# SCH_openELECTRO_-_ArduinoUNO_-_OVEN_2022.net
KiCad netlist of a schematic drawn in EasyEDA
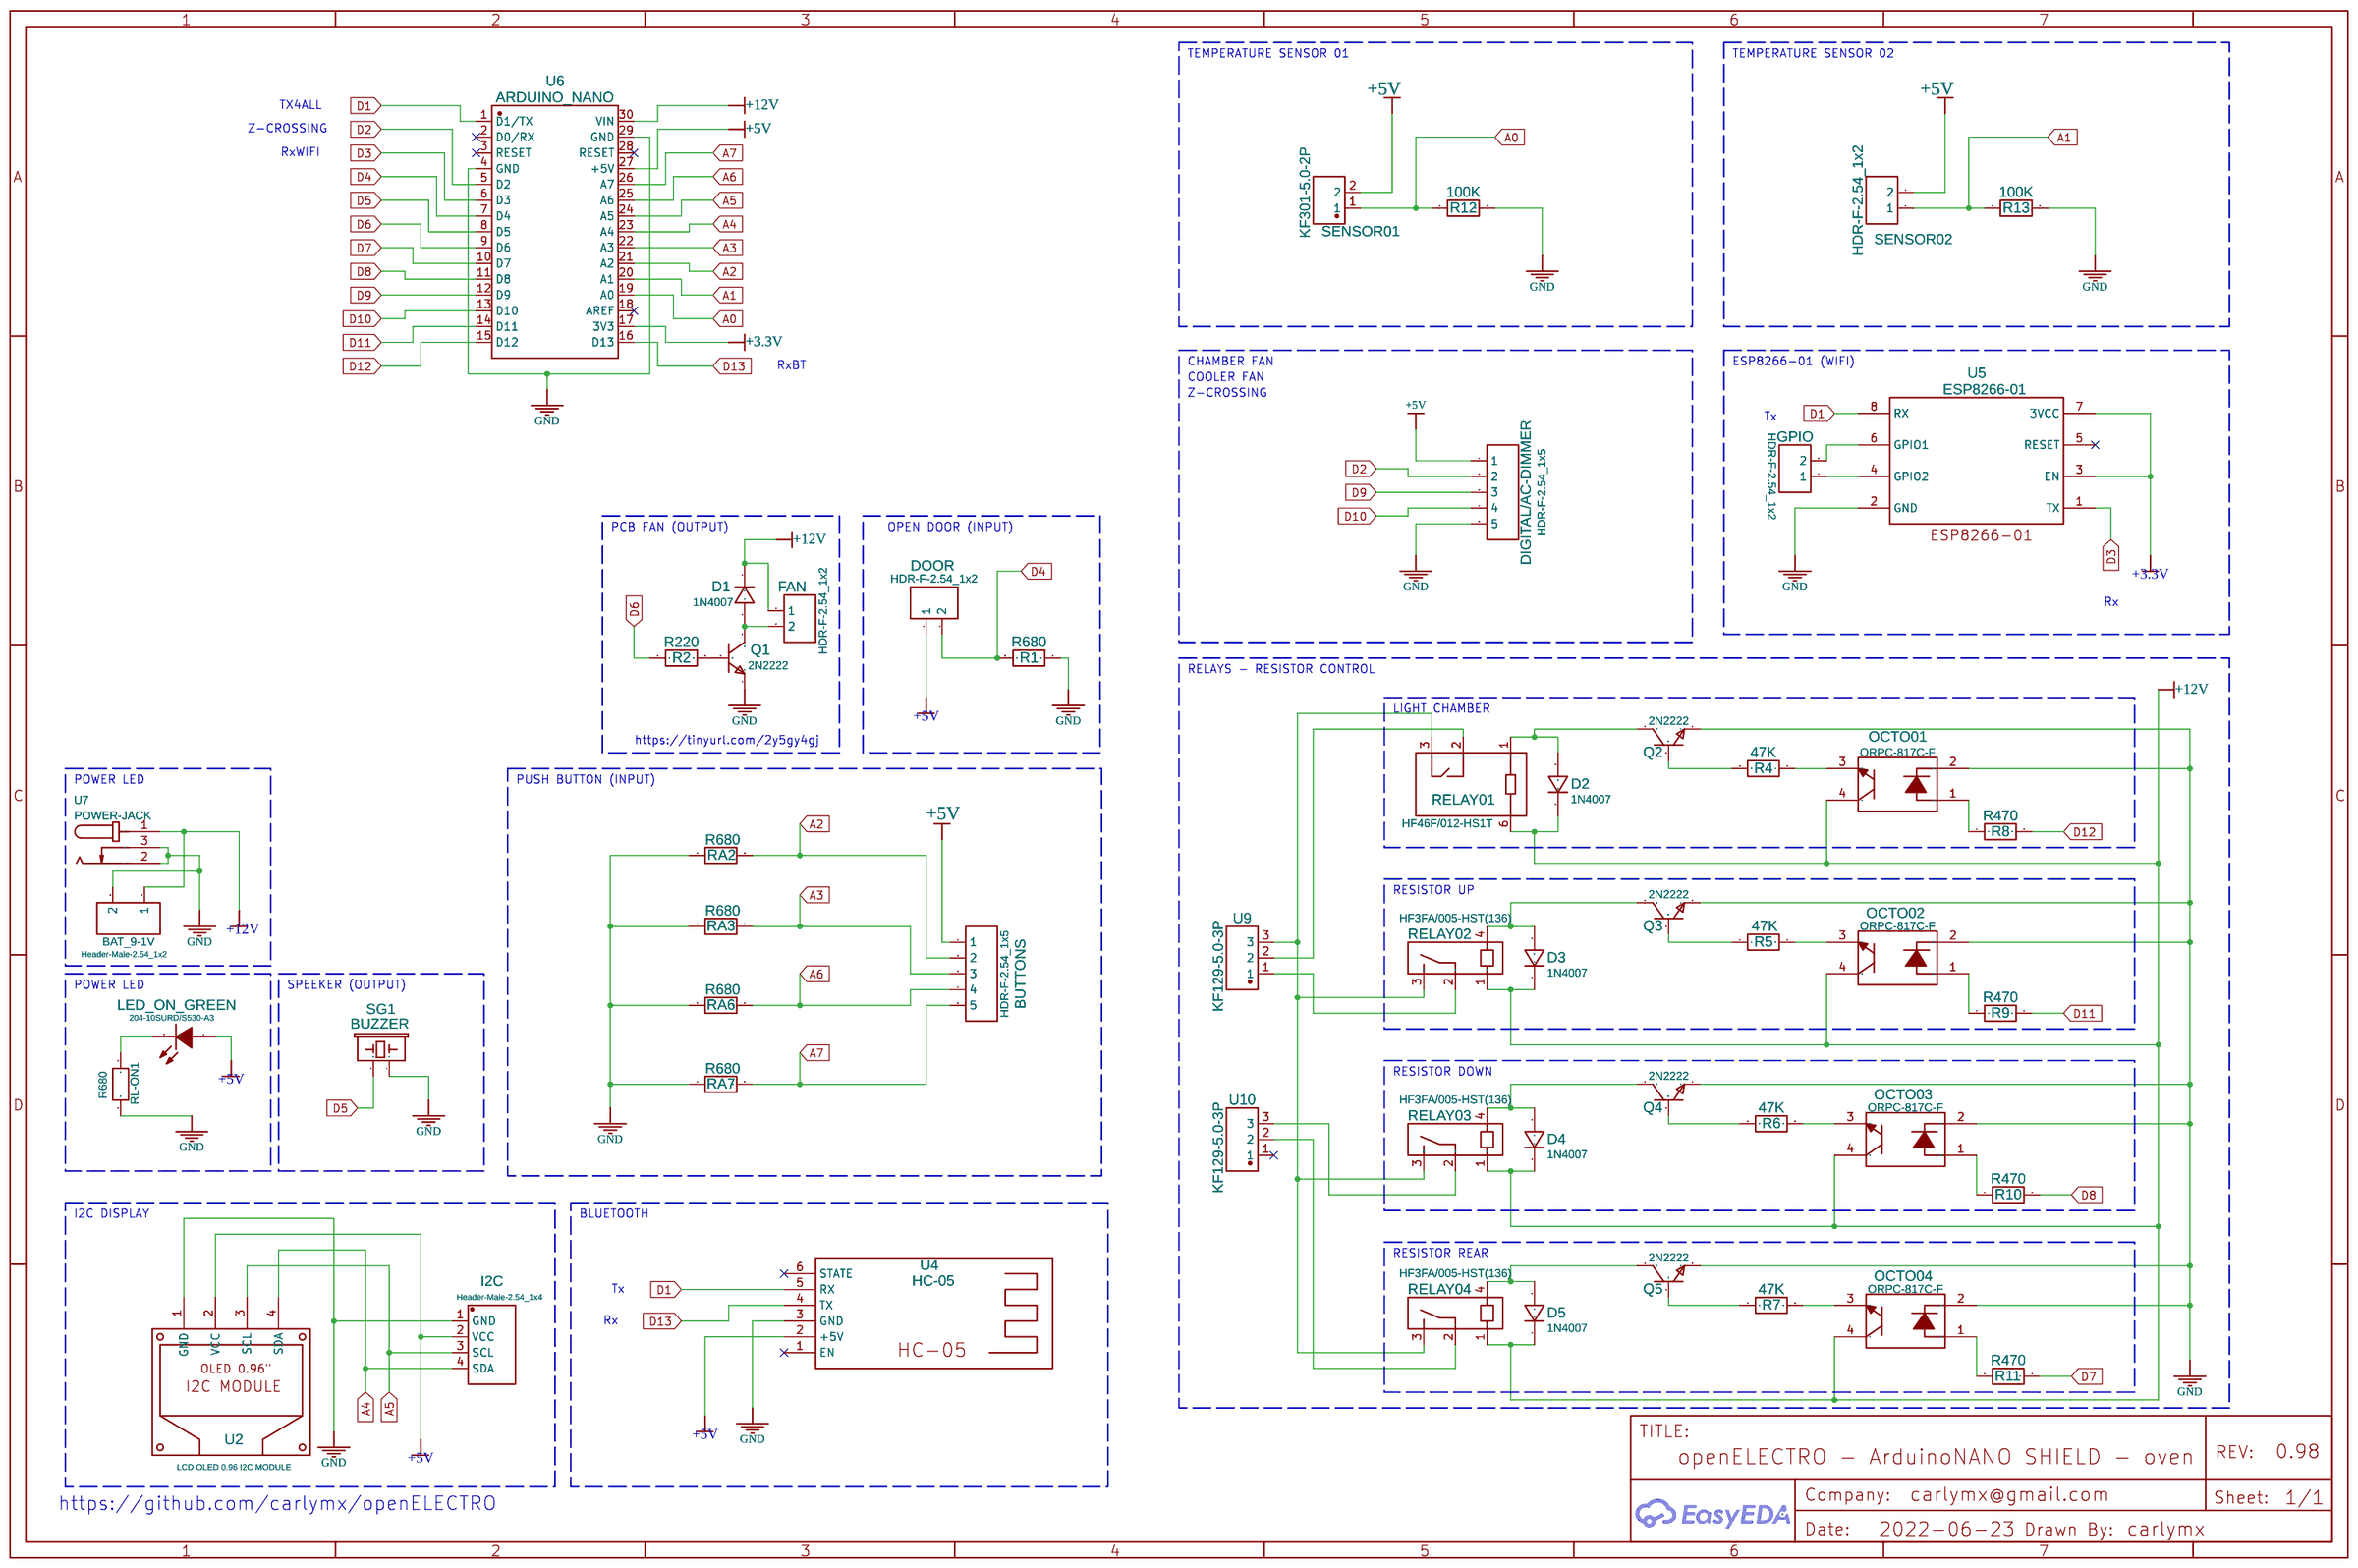
[diagram p0: schematic sheet]

(export (version "E")
  (design (tool "Eeschema 10.0.6"))
  (components
    (comp (ref "BAT_9-1V")
      (value "Header-Male-2.54_1x2")
      (fields (field (name "BOM_Manufacturer Part") "826629-2") (field (name "BOM_Supplier Part") "C86471"))
      (libsource (lib "") (part "Unknown_65_-400"))
    )
    (comp (ref "BUTTONS")
      (value "HDR-F-2.54_1x5")
      (fields (field (name "BOM_Supplier Part") "C50950"))
      (libsource (lib "") (part "HDR-F-2.54_1x5"))
    )
    (comp (ref "D1")
      (value "1N4007")
      (fields (field (name "BOM_Supplier Part") "C106903"))
      (libsource (lib "") (part "1N4007"))
    )
    (comp (ref "D2")
      (value "1N4007")
      (fields (field (name "BOM_Supplier Part") "C106903"))
      (libsource (lib "") (part "1N4007_1"))
    )
    (comp (ref "D3")
      (value "1N4007")
      (fields (field (name "BOM_Supplier Part") "C106903"))
      (libsource (lib "") (part "1N4007_1"))
    )
    (comp (ref "D4")
      (value "1N4007")
      (fields (field (name "BOM_Supplier Part") "C106903"))
      (libsource (lib "") (part "1N4007_1"))
    )
    (comp (ref "D5")
      (value "1N4007")
      (fields (field (name "BOM_Supplier Part") "C106903"))
      (libsource (lib "") (part "1N4007_1"))
    )
    (comp (ref "DIGITAL/AC-DIMMER")
      (value "HDR-F-2.54_1x5")
      (fields (field (name "BOM_Supplier Part") "C50950"))
      (libsource (lib "") (part "HDR-F-2.54_1x5_1"))
    )
    (comp (ref "DOOR")
      (value "HDR-F-2.54_1x2")
      (fields (field (name "BOM_Supplier Part") "C49661"))
      (libsource (lib "") (part "HDR-F-2.54_1x2_3"))
    )
    (comp (ref "FAN")
      (value "HDR-F-2.54_1x2")
      (fields (field (name "BOM_Supplier Part") "C49661"))
      (libsource (lib "") (part "HDR-F-2.54_1x2_1"))
    )
    (comp (ref "GPIO")
      (value "HDR-F-2.54_1x2")
      (fields (field (name "BOM_Supplier Part") "C49661"))
      (libsource (lib "") (part "HDR-F-2.54_1x2"))
    )
    (comp (ref "I2C")
      (value "Header-Male-2.54_1x4")
      (fields
        (field (name "BOM_Manufacturer Part") "210S-1*4P L=11.6MMGold-plated black")
        (field (name "BOM_Supplier Part") "C124378")
      )
      (libsource (lib "") (part "Unknown_290_-125"))
    )
    (comp (ref "LED_ON_GREEN")
      (value "204-10SURD/S530-A3")
      (fields (field (name "BOM_Supplier Part") "C99772"))
      (libsource (lib "") (part "Unknown_100_-315"))
    )
    (comp (ref "OCTO01")
      (value "ORPC-817C-F")
      (fields (field (name "BOM_Supplier Part") "C2842770"))
      (libsource (lib "") (part "ORPC-817C-F"))
    )
    (comp (ref "OCTO02")
      (value "ORPC-817C-F")
      (fields (field (name "BOM_Supplier Part") "C2842770"))
      (libsource (lib "") (part "ORPC-817C-F"))
    )
    (comp (ref "OCTO03")
      (value "ORPC-817C-F")
      (fields (field (name "BOM_Supplier Part") "C2842770"))
      (libsource (lib "") (part "ORPC-817C-F"))
    )
    (comp (ref "OCTO04")
      (value "ORPC-817C-F")
      (fields (field (name "BOM_Supplier Part") "C2842770"))
      (libsource (lib "") (part "ORPC-817C-F"))
    )
    (comp (ref "Q1")
      (value "2N2222")
      (fields (field (name "BOM_Supplier Part") "C118536"))
      (libsource (lib "") (part "2N2222_1"))
    )
    (comp (ref "Q2")
      (value "2N2222")
      (fields (field (name "BOM_Supplier Part") "C118536"))
      (libsource (lib "") (part "2N2222"))
    )
    (comp (ref "Q3")
      (value "2N2222")
      (fields (field (name "BOM_Supplier Part") "C118536"))
      (libsource (lib "") (part "2N2222"))
    )
    (comp (ref "Q4")
      (value "2N2222")
      (fields (field (name "BOM_Supplier Part") "C118536"))
      (libsource (lib "") (part "2N2222"))
    )
    (comp (ref "Q5")
      (value "2N2222")
      (fields (field (name "BOM_Supplier Part") "C118536"))
      (libsource (lib "") (part "2N2222"))
    )
    (comp (ref "R1") (value "R680") (libsource (lib "") (part "R_0603_EU_1")))
    (comp (ref "R2") (value "R220") (libsource (lib "") (part "R_0603_EU")))
    (comp (ref "R4") (value "47K") (libsource (lib "") (part "R_0603_EU_1")))
    (comp (ref "R5") (value "47K") (libsource (lib "") (part "R_0603_EU")))
    (comp (ref "R6") (value "47K") (libsource (lib "") (part "R_0603_EU")))
    (comp (ref "R7") (value "47K") (libsource (lib "") (part "R_0603_EU")))
    (comp (ref "R8") (value "R470") (libsource (lib "") (part "R_0603_EU")))
    (comp (ref "R9") (value "R470") (libsource (lib "") (part "R_0603_EU")))
    (comp (ref "R10") (value "R470") (libsource (lib "") (part "R_0603_EU")))
    (comp (ref "R11") (value "R470") (libsource (lib "") (part "R_0603_EU")))
    (comp (ref "R12") (value "100K") (libsource (lib "") (part "R_0603_EU")))
    (comp (ref "R13") (value "100K") (libsource (lib "") (part "R_0603_EU")))
    (comp (ref "RA2") (value "R680") (libsource (lib "") (part "Res_AXIAL-0.3(1/8W)_EU")))
    (comp (ref "RA3") (value "R680") (libsource (lib "") (part "Res_AXIAL-0.3(1/8W)_EU")))
    (comp (ref "RA6") (value "R680") (libsource (lib "") (part "Res_AXIAL-0.3(1/8W)_EU")))
    (comp (ref "RA7") (value "R680") (libsource (lib "") (part "Res_AXIAL-0.3(1/8W)_EU")))
    (comp (ref "RELAY01")
      (value "HF46F/012-HS1T")
      (fields (field (name "BOM_Supplier Part") "C2976852"))
      (libsource (lib "") (part "HF46F/012-HS1T"))
    )
    (comp (ref "RELAY02")
      (value "HF3FA/005-HST(136)")
      (fields (field (name "BOM_Supplier Part") "C712707"))
      (libsource (lib "") (part "HF3FA/005-HST(136)"))
    )
    (comp (ref "RELAY03")
      (value "HF3FA/005-HST(136)")
      (fields (field (name "BOM_Supplier Part") "C712707"))
      (libsource (lib "") (part "HF3FA/005-HST(136)"))
    )
    (comp (ref "RELAY04")
      (value "HF3FA/005-HST(136)")
      (fields (field (name "BOM_Supplier Part") "C712707"))
      (libsource (lib "") (part "HF3FA/005-HST(136)"))
    )
    (comp (ref "RL-ON1") (value "R680") (libsource (lib "") (part "Res_AXIAL-0.3(1/8W)_EU_1")))
    (comp (ref "SENSOR01")
      (value "KF301-5.0-2P")
      (fields (field (name "BOM_Supplier Part") "C474881"))
      (libsource (lib "") (part "KF301-5.0-2P"))
    )
    (comp (ref "SENSOR02")
      (value "HDR-F-2.54_1x2")
      (fields (field (name "BOM_Supplier Part") "C49661"))
      (libsource (lib "") (part "HDR-F-2.54_1x2_2"))
    )
    (comp (ref "SG1") (value "BUZZER") (libsource (lib "") (part "Unknown_225_-305")))
    (comp (ref "U2")
      (value "LCD OLED 0.96 I2C MODULE")
      (fields (field (name "BOM_Manufacturer Part") "Control Chip SSD1306"))
      (libsource (lib "") (part "Unknown_80_-135"))
    )
    (comp (ref "U4") (value "HC-05") (libsource (lib "") (part "Unknown_500_-180")))
    (comp (ref "U5") (value "ESP8266-01") (libsource (lib "") (part "ESP8266-01")))
    (comp (ref "U6")
      (value "ARDUINO_NANO")
      (fields (field (name "BOM_Supplier Part") "C9900017879"))
      (libsource (lib "") (part "ARDUINO_NANO"))
    )
    (comp (ref "U7")
      (value "POWER-JACK")
      (fields (field (name "BOM_Supplier Part") "C9900001795"))
      (libsource (lib "") (part "POWER-JACK"))
    )
    (comp (ref "U9")
      (value "KF129-5.0-3P")
      (fields (field (name "BOM_Supplier Part") "C475091"))
      (libsource (lib "") (part "KF129-5.0-3P"))
    )
    (comp (ref "U10")
      (value "KF129-5.0-3P")
      (fields (field (name "BOM_Supplier Part") "C475091"))
      (libsource (lib "") (part "KF129-5.0-3P"))
    )
  )
  (nets
    (net (code "1") (name "+3.3V") (class "Default")
      (node (ref "U5") (pin "3") (pinfunction "EN_3") (pintype "unspecified"))
      (node (ref "U5") (pin "7") (pinfunction "3VCC_7") (pintype "unspecified"))
      (node (ref "U6") (pin "17") (pinfunction "3V3_17") (pintype "unspecified"))
    )
    (net (code "2") (name "+5V") (class "Default")
      (node (ref "BUTTONS") (pin "1") (pinfunction "1_1") (pintype "unspecified"))
      (node (ref "DIGITAL/AC-DIMMER") (pin "1") (pinfunction "1_1") (pintype "unspecified"))
      (node (ref "DOOR") (pin "1") (pinfunction "1_1") (pintype "input"))
      (node (ref "I2C") (pin "2") (pinfunction "VCC_2") (pintype "unspecified"))
      (node (ref "LED_ON_GREEN") (pin "1") (pinfunction "A_1") (pintype "unspecified"))
      (node (ref "SENSOR01") (pin "2") (pinfunction "2_2") (pintype "unspecified"))
      (node (ref "SENSOR02") (pin "2") (pinfunction "2_2") (pintype "input"))
      (node (ref "U2") (pin "2") (pinfunction "VCC_2") (pintype "unspecified"))
      (node (ref "U4") (pin "2") (pinfunction "+5V_2") (pintype "unspecified"))
      (node (ref "U6") (pin "27") (pinfunction "+5V_27") (pintype "unspecified"))
    )
    (net (code "3") (name "+12V") (class "Default")
      (node (ref "BAT_9-1V") (pin "1") (pinfunction "1_1") (pintype "unspecified"))
      (node (ref "D1") (pin "1") (pinfunction "1_1") (pintype "unspecified"))
      (node (ref "D2") (pin "1") (pinfunction "1_1") (pintype "unspecified"))
      (node (ref "D3") (pin "1") (pinfunction "1_1") (pintype "unspecified"))
      (node (ref "D4") (pin "1") (pinfunction "1_1") (pintype "unspecified"))
      (node (ref "D5") (pin "1") (pinfunction "1_1") (pintype "unspecified"))
      (node (ref "FAN") (pin "1") (pinfunction "1_1") (pintype "input"))
      (node (ref "OCTO01") (pin "4") (pinfunction "4_4") (pintype "unspecified"))
      (node (ref "OCTO02") (pin "4") (pinfunction "4_4") (pintype "unspecified"))
      (node (ref "OCTO03") (pin "4") (pinfunction "4_4") (pintype "unspecified"))
      (node (ref "OCTO04") (pin "4") (pinfunction "4_4") (pintype "unspecified"))
      (node (ref "RELAY01") (pin "6") (pinfunction "6_6") (pintype "unspecified"))
      (node (ref "RELAY02") (pin "1") (pinfunction "1_1") (pintype "unspecified"))
      (node (ref "RELAY03") (pin "1") (pinfunction "1_1") (pintype "unspecified"))
      (node (ref "RELAY04") (pin "1") (pinfunction "1_1") (pintype "unspecified"))
      (node (ref "U6") (pin "30") (pinfunction "VIN_30") (pintype "unspecified"))
      (node (ref "U7") (pin "1") (pinfunction "1_1") (pintype "unspecified"))
    )
    (net (code "4") (name "A0") (class "Default")
      (node (ref "R12") (pin "1") (pinfunction "1_1") (pintype "unspecified"))
      (node (ref "SENSOR01") (pin "1") (pinfunction "1_1") (pintype "unspecified"))
      (node (ref "U6") (pin "19") (pinfunction "A0_19") (pintype "unspecified"))
    )
    (net (code "5") (name "A1") (class "Default")
      (node (ref "R13") (pin "1") (pinfunction "1_1") (pintype "unspecified"))
      (node (ref "SENSOR02") (pin "1") (pinfunction "1_1") (pintype "input"))
      (node (ref "U6") (pin "20") (pinfunction "A1_20") (pintype "unspecified"))
    )
    (net (code "6") (name "A2") (class "Default")
      (node (ref "BUTTONS") (pin "2") (pinfunction "2_2") (pintype "unspecified"))
      (node (ref "RA2") (pin "2") (pinfunction "2_2") (pintype "unspecified"))
      (node (ref "U6") (pin "21") (pinfunction "A2_21") (pintype "unspecified"))
    )
    (net (code "7") (name "A3") (class "Default")
      (node (ref "BUTTONS") (pin "3") (pinfunction "3_3") (pintype "unspecified"))
      (node (ref "RA3") (pin "2") (pinfunction "2_2") (pintype "unspecified"))
      (node (ref "U6") (pin "22") (pinfunction "A3_22") (pintype "unspecified"))
    )
    (net (code "8") (name "A4") (class "Default")
      (node (ref "I2C") (pin "4") (pinfunction "SDA_4") (pintype "unspecified"))
      (node (ref "U2") (pin "4") (pinfunction "SDA_4") (pintype "unspecified"))
      (node (ref "U6") (pin "23") (pinfunction "A4_23") (pintype "unspecified"))
    )
    (net (code "9") (name "A5") (class "Default")
      (node (ref "I2C") (pin "3") (pinfunction "SCL_3") (pintype "unspecified"))
      (node (ref "U2") (pin "3") (pinfunction "SCL_3") (pintype "unspecified"))
      (node (ref "U6") (pin "24") (pinfunction "A5_24") (pintype "unspecified"))
    )
    (net (code "10") (name "A6") (class "Default")
      (node (ref "BUTTONS") (pin "4") (pinfunction "4_4") (pintype "unspecified"))
      (node (ref "RA6") (pin "2") (pinfunction "2_2") (pintype "unspecified"))
      (node (ref "U6") (pin "25") (pinfunction "A6_25") (pintype "unspecified"))
    )
    (net (code "11") (name "A7") (class "Default")
      (node (ref "BUTTONS") (pin "5") (pinfunction "5_5") (pintype "unspecified"))
      (node (ref "RA7") (pin "2") (pinfunction "2_2") (pintype "unspecified"))
      (node (ref "U6") (pin "26") (pinfunction "A7_26") (pintype "unspecified"))
    )
    (net (code "12") (name "D1") (class "Default")
      (node (ref "U4") (pin "5") (pinfunction "RX_5") (pintype "unspecified"))
      (node (ref "U5") (pin "8") (pinfunction "RX_8") (pintype "unspecified"))
      (node (ref "U6") (pin "1") (pinfunction "D1/TX_1") (pintype "unspecified"))
    )
    (net (code "13") (name "D2") (class "Default")
      (node (ref "DIGITAL/AC-DIMMER") (pin "2") (pinfunction "2_2") (pintype "unspecified"))
      (node (ref "U6") (pin "5") (pinfunction "D2_5") (pintype "unspecified"))
    )
    (net (code "14") (name "D3") (class "Default")
      (node (ref "U5") (pin "1") (pinfunction "TX_1") (pintype "unspecified"))
      (node (ref "U6") (pin "6") (pinfunction "D3_6") (pintype "unspecified"))
    )
    (net (code "15") (name "D4") (class "Default")
      (node (ref "DOOR") (pin "2") (pinfunction "2_2") (pintype "input"))
      (node (ref "R1") (pin "2") (pinfunction "2_2") (pintype "unspecified"))
      (node (ref "U6") (pin "7") (pinfunction "D4_7") (pintype "unspecified"))
    )
    (net (code "16") (name "D5") (class "Default")
      (node (ref "SG1") (pin "+") (pinfunction "1_+") (pintype "unspecified"))
      (node (ref "U6") (pin "8") (pinfunction "D5_8") (pintype "unspecified"))
    )
    (net (code "17") (name "D6") (class "Default")
      (node (ref "R2") (pin "1") (pinfunction "1_1") (pintype "unspecified"))
      (node (ref "U6") (pin "9") (pinfunction "D6_9") (pintype "unspecified"))
    )
    (net (code "18") (name "D7") (class "Default")
      (node (ref "R11") (pin "2") (pinfunction "2_2") (pintype "unspecified"))
      (node (ref "U6") (pin "10") (pinfunction "D7_10") (pintype "unspecified"))
    )
    (net (code "19") (name "D8") (class "Default")
      (node (ref "R10") (pin "2") (pinfunction "2_2") (pintype "unspecified"))
      (node (ref "U6") (pin "11") (pinfunction "D8_11") (pintype "unspecified"))
    )
    (net (code "20") (name "D9") (class "Default")
      (node (ref "DIGITAL/AC-DIMMER") (pin "3") (pinfunction "3_3") (pintype "unspecified"))
      (node (ref "U6") (pin "12") (pinfunction "D9_12") (pintype "unspecified"))
    )
    (net (code "21") (name "D10") (class "Default")
      (node (ref "DIGITAL/AC-DIMMER") (pin "4") (pinfunction "4_4") (pintype "unspecified"))
      (node (ref "U6") (pin "13") (pinfunction "D10_13") (pintype "unspecified"))
    )
    (net (code "22") (name "D11") (class "Default")
      (node (ref "R9") (pin "2") (pinfunction "2_2") (pintype "unspecified"))
      (node (ref "U6") (pin "14") (pinfunction "D11_14") (pintype "unspecified"))
    )
    (net (code "23") (name "D12") (class "Default")
      (node (ref "R8") (pin "2") (pinfunction "2_2") (pintype "unspecified"))
      (node (ref "U6") (pin "15") (pinfunction "D12_15") (pintype "unspecified"))
    )
    (net (code "24") (name "D13") (class "Default")
      (node (ref "U4") (pin "4") (pinfunction "TX_4") (pintype "unspecified"))
      (node (ref "U6") (pin "16") (pinfunction "D13_16") (pintype "unspecified"))
    )
    (net (code "25") (name "GND") (class "Default")
      (node (ref "BAT_9-1V") (pin "2") (pinfunction "2_2") (pintype "unspecified"))
      (node (ref "DIGITAL/AC-DIMMER") (pin "5") (pinfunction "5_5") (pintype "unspecified"))
      (node (ref "I2C") (pin "1") (pinfunction "GND_1") (pintype "unspecified"))
      (node (ref "OCTO01") (pin "2") (pinfunction "2_2") (pintype "unspecified"))
      (node (ref "OCTO02") (pin "2") (pinfunction "2_2") (pintype "unspecified"))
      (node (ref "OCTO03") (pin "2") (pinfunction "2_2") (pintype "unspecified"))
      (node (ref "OCTO04") (pin "2") (pinfunction "2_2") (pintype "unspecified"))
      (node (ref "Q1") (pin "1") (pinfunction "E_1") (pintype "unspecified"))
      (node (ref "Q2") (pin "1") (pinfunction "E_1") (pintype "unspecified"))
      (node (ref "Q3") (pin "1") (pinfunction "E_1") (pintype "unspecified"))
      (node (ref "Q4") (pin "1") (pinfunction "E_1") (pintype "unspecified"))
      (node (ref "Q5") (pin "1") (pinfunction "E_1") (pintype "unspecified"))
      (node (ref "R1") (pin "1") (pinfunction "1_1") (pintype "unspecified"))
      (node (ref "R12") (pin "2") (pinfunction "2_2") (pintype "unspecified"))
      (node (ref "R13") (pin "2") (pinfunction "2_2") (pintype "unspecified"))
      (node (ref "RA2") (pin "1") (pinfunction "1_1") (pintype "unspecified"))
      (node (ref "RA3") (pin "1") (pinfunction "1_1") (pintype "unspecified"))
      (node (ref "RA6") (pin "1") (pinfunction "1_1") (pintype "unspecified"))
      (node (ref "RA7") (pin "1") (pinfunction "1_1") (pintype "unspecified"))
      (node (ref "RL-ON1") (pin "1") (pinfunction "1_1") (pintype "unspecified"))
      (node (ref "SG1") (pin "-") (pinfunction "2_-") (pintype "unspecified"))
      (node (ref "U2") (pin "1") (pinfunction "GND_1") (pintype "unspecified"))
      (node (ref "U4") (pin "3") (pinfunction "GND_3") (pintype "unspecified"))
      (node (ref "U5") (pin "2") (pinfunction "GND_2") (pintype "unspecified"))
      (node (ref "U6") (pin "29") (pinfunction "GND_29") (pintype "unspecified"))
      (node (ref "U6") (pin "4") (pinfunction "GND_4") (pintype "unspecified"))
      (node (ref "U7") (pin "2") (pinfunction "2_2") (pintype "unspecified"))
      (node (ref "U7") (pin "3") (pinfunction "3_3") (pintype "unspecified"))
    )
    (net (code "26") (name "Net-(LED_ON_GREEN-K)") (class "Default")
      (node (ref "LED_ON_GREEN") (pin "2") (pinfunction "K_2") (pintype "unspecified"))
      (node (ref "RL-ON1") (pin "2") (pinfunction "2_2") (pintype "unspecified"))
    )
    (net (code "27") (name "Net-(OCTO01-Pad1)") (class "Default")
      (node (ref "OCTO01") (pin "1") (pinfunction "1_1") (pintype "unspecified"))
      (node (ref "R8") (pin "1") (pinfunction "1_1") (pintype "unspecified"))
    )
    (net (code "28") (name "Net-(OCTO01-Pad3)") (class "Default")
      (node (ref "OCTO01") (pin "3") (pinfunction "3_3") (pintype "unspecified"))
      (node (ref "R4") (pin "1") (pinfunction "1_1") (pintype "unspecified"))
    )
    (net (code "29") (name "Net-(OCTO02-Pad1)") (class "Default")
      (node (ref "OCTO02") (pin "1") (pinfunction "1_1") (pintype "unspecified"))
      (node (ref "R9") (pin "1") (pinfunction "1_1") (pintype "unspecified"))
    )
    (net (code "30") (name "Net-(OCTO02-Pad3)") (class "Default")
      (node (ref "OCTO02") (pin "3") (pinfunction "3_3") (pintype "unspecified"))
      (node (ref "R5") (pin "2") (pinfunction "2_2") (pintype "unspecified"))
    )
    (net (code "31") (name "Net-(OCTO03-Pad1)") (class "Default")
      (node (ref "OCTO03") (pin "1") (pinfunction "1_1") (pintype "unspecified"))
      (node (ref "R10") (pin "1") (pinfunction "1_1") (pintype "unspecified"))
    )
    (net (code "32") (name "Net-(OCTO03-Pad3)") (class "Default")
      (node (ref "OCTO03") (pin "3") (pinfunction "3_3") (pintype "unspecified"))
      (node (ref "R6") (pin "2") (pinfunction "2_2") (pintype "unspecified"))
    )
    (net (code "33") (name "Net-(OCTO04-Pad1)") (class "Default")
      (node (ref "OCTO04") (pin "1") (pinfunction "1_1") (pintype "unspecified"))
      (node (ref "R11") (pin "1") (pinfunction "1_1") (pintype "unspecified"))
    )
    (net (code "34") (name "Net-(OCTO04-Pad3)") (class "Default")
      (node (ref "OCTO04") (pin "3") (pinfunction "3_3") (pintype "unspecified"))
      (node (ref "R7") (pin "2") (pinfunction "2_2") (pintype "unspecified"))
    )
    (net (code "35") (name "Net-(Q1-B)") (class "Default")
      (node (ref "Q1") (pin "2") (pinfunction "B_2") (pintype "unspecified"))
      (node (ref "R2") (pin "2") (pinfunction "2_2") (pintype "unspecified"))
    )
    (net (code "36") (name "Net-(Q1-C)") (class "Default")
      (node (ref "D1") (pin "2") (pinfunction "2_2") (pintype "unspecified"))
      (node (ref "FAN") (pin "2") (pinfunction "2_2") (pintype "input"))
      (node (ref "Q1") (pin "3") (pinfunction "C_3") (pintype "unspecified"))
    )
    (net (code "37") (name "Net-(Q2-B)") (class "Default")
      (node (ref "Q2") (pin "2") (pinfunction "B_2") (pintype "unspecified"))
      (node (ref "R4") (pin "2") (pinfunction "2_2") (pintype "unspecified"))
    )
    (net (code "38") (name "Net-(Q2-C)") (class "Default")
      (node (ref "D2") (pin "2") (pinfunction "2_2") (pintype "unspecified"))
      (node (ref "Q2") (pin "3") (pinfunction "C_3") (pintype "unspecified"))
      (node (ref "RELAY01") (pin "1") (pinfunction "1_1") (pintype "unspecified"))
    )
    (net (code "39") (name "Net-(Q3-B)") (class "Default")
      (node (ref "Q3") (pin "2") (pinfunction "B_2") (pintype "unspecified"))
      (node (ref "R5") (pin "1") (pinfunction "1_1") (pintype "unspecified"))
    )
    (net (code "40") (name "Net-(Q3-C)") (class "Default")
      (node (ref "D3") (pin "2") (pinfunction "2_2") (pintype "unspecified"))
      (node (ref "Q3") (pin "3") (pinfunction "C_3") (pintype "unspecified"))
      (node (ref "RELAY02") (pin "4") (pinfunction "4_4") (pintype "unspecified"))
    )
    (net (code "41") (name "Net-(Q4-B)") (class "Default")
      (node (ref "Q4") (pin "2") (pinfunction "B_2") (pintype "unspecified"))
      (node (ref "R6") (pin "1") (pinfunction "1_1") (pintype "unspecified"))
    )
    (net (code "42") (name "Net-(Q4-C)") (class "Default")
      (node (ref "D4") (pin "2") (pinfunction "2_2") (pintype "unspecified"))
      (node (ref "Q4") (pin "3") (pinfunction "C_3") (pintype "unspecified"))
      (node (ref "RELAY03") (pin "4") (pinfunction "4_4") (pintype "unspecified"))
    )
    (net (code "43") (name "Net-(Q5-B)") (class "Default")
      (node (ref "Q5") (pin "2") (pinfunction "B_2") (pintype "unspecified"))
      (node (ref "R7") (pin "1") (pinfunction "1_1") (pintype "unspecified"))
    )
    (net (code "44") (name "Net-(Q5-C)") (class "Default")
      (node (ref "D5") (pin "2") (pinfunction "2_2") (pintype "unspecified"))
      (node (ref "Q5") (pin "3") (pinfunction "C_3") (pintype "unspecified"))
      (node (ref "RELAY04") (pin "4") (pinfunction "4_4") (pintype "unspecified"))
    )
    (net (code "45") (name "Net-(RELAY01-Pad2)") (class "Default")
      (node (ref "RELAY01") (pin "2") (pinfunction "2_2") (pintype "unspecified"))
      (node (ref "U9") (pin "2") (pinfunction "2_2") (pintype "unspecified"))
    )
    (net (code "46") (name "Net-(RELAY01-Pad3)") (class "Default")
      (node (ref "RELAY01") (pin "3") (pinfunction "3_3") (pintype "unspecified"))
      (node (ref "RELAY02") (pin "3") (pinfunction "3_3") (pintype "unspecified"))
      (node (ref "RELAY03") (pin "3") (pinfunction "3_3") (pintype "unspecified"))
      (node (ref "RELAY04") (pin "3") (pinfunction "3_3") (pintype "unspecified"))
      (node (ref "U9") (pin "3") (pinfunction "3_3") (pintype "unspecified"))
    )
    (net (code "47") (name "Net-(RELAY02-Pad2)") (class "Default")
      (node (ref "RELAY02") (pin "2") (pinfunction "2_2") (pintype "unspecified"))
      (node (ref "U9") (pin "1") (pinfunction "1_1") (pintype "unspecified"))
    )
    (net (code "48") (name "Net-(RELAY03-Pad2)") (class "Default")
      (node (ref "RELAY03") (pin "2") (pinfunction "2_2") (pintype "unspecified"))
      (node (ref "U10") (pin "3") (pinfunction "3_3") (pintype "unspecified"))
    )
    (net (code "49") (name "Net-(RELAY04-Pad2)") (class "Default")
      (node (ref "RELAY04") (pin "2") (pinfunction "2_2") (pintype "unspecified"))
      (node (ref "U10") (pin "2") (pinfunction "2_2") (pintype "unspecified"))
    )
    (net (code "50") (name "Net-(U5-GPIO1)") (class "Default")
      (node (ref "GPIO") (pin "2") (pinfunction "2_2") (pintype "input"))
      (node (ref "U5") (pin "6") (pinfunction "GPIO1_6") (pintype "unspecified"))
    )
    (net (code "51") (name "Net-(U5-GPIO2)") (class "Default")
      (node (ref "GPIO") (pin "1") (pinfunction "1_1") (pintype "input"))
      (node (ref "U5") (pin "4") (pinfunction "GPIO2_4") (pintype "unspecified"))
    )
    (net (code "52") (name "unconnected-(U4-EN-Pad1)") (class "Default")
      (node (ref "U4") (pin "1") (pinfunction "EN_1") (pintype "unspecified+no_connect"))
    )
    (net (code "53") (name "unconnected-(U4-STATE-Pad6)") (class "Default")
      (node (ref "U4") (pin "6") (pinfunction "STATE_6") (pintype "unspecified+no_connect"))
    )
    (net (code "54") (name "unconnected-(U5-RESET-Pad5)") (class "Default")
      (node (ref "U5") (pin "5") (pinfunction "RESET_5") (pintype "unspecified+no_connect"))
    )
    (net (code "55") (name "unconnected-(U6-AREF-Pad18)") (class "Default")
      (node (ref "U6") (pin "18") (pinfunction "AREF_18") (pintype "unspecified+no_connect"))
    )
    (net (code "56") (name "unconnected-(U6-D0{slash}RX-Pad2)") (class "Default")
      (node (ref "U6") (pin "2") (pinfunction "D0/RX_2") (pintype "unspecified+no_connect"))
    )
    (net (code "57") (name "unconnected-(U6-RESET-Pad3)") (class "Default")
      (node (ref "U6") (pin "3") (pinfunction "RESET_3") (pintype "unspecified+no_connect"))
    )
    (net (code "58") (name "unconnected-(U6-RESET-Pad28)") (class "Default")
      (node (ref "U6") (pin "28") (pinfunction "RESET_28") (pintype "unspecified+no_connect"))
    )
    (net (code "59") (name "unconnected-(U10-Pad1)") (class "Default")
      (node (ref "U10") (pin "1") (pinfunction "1_1") (pintype "unspecified+no_connect"))
    )
  )
)
